# V1_0.net
KiCad netlist of a schematic drawn in Altium Designer
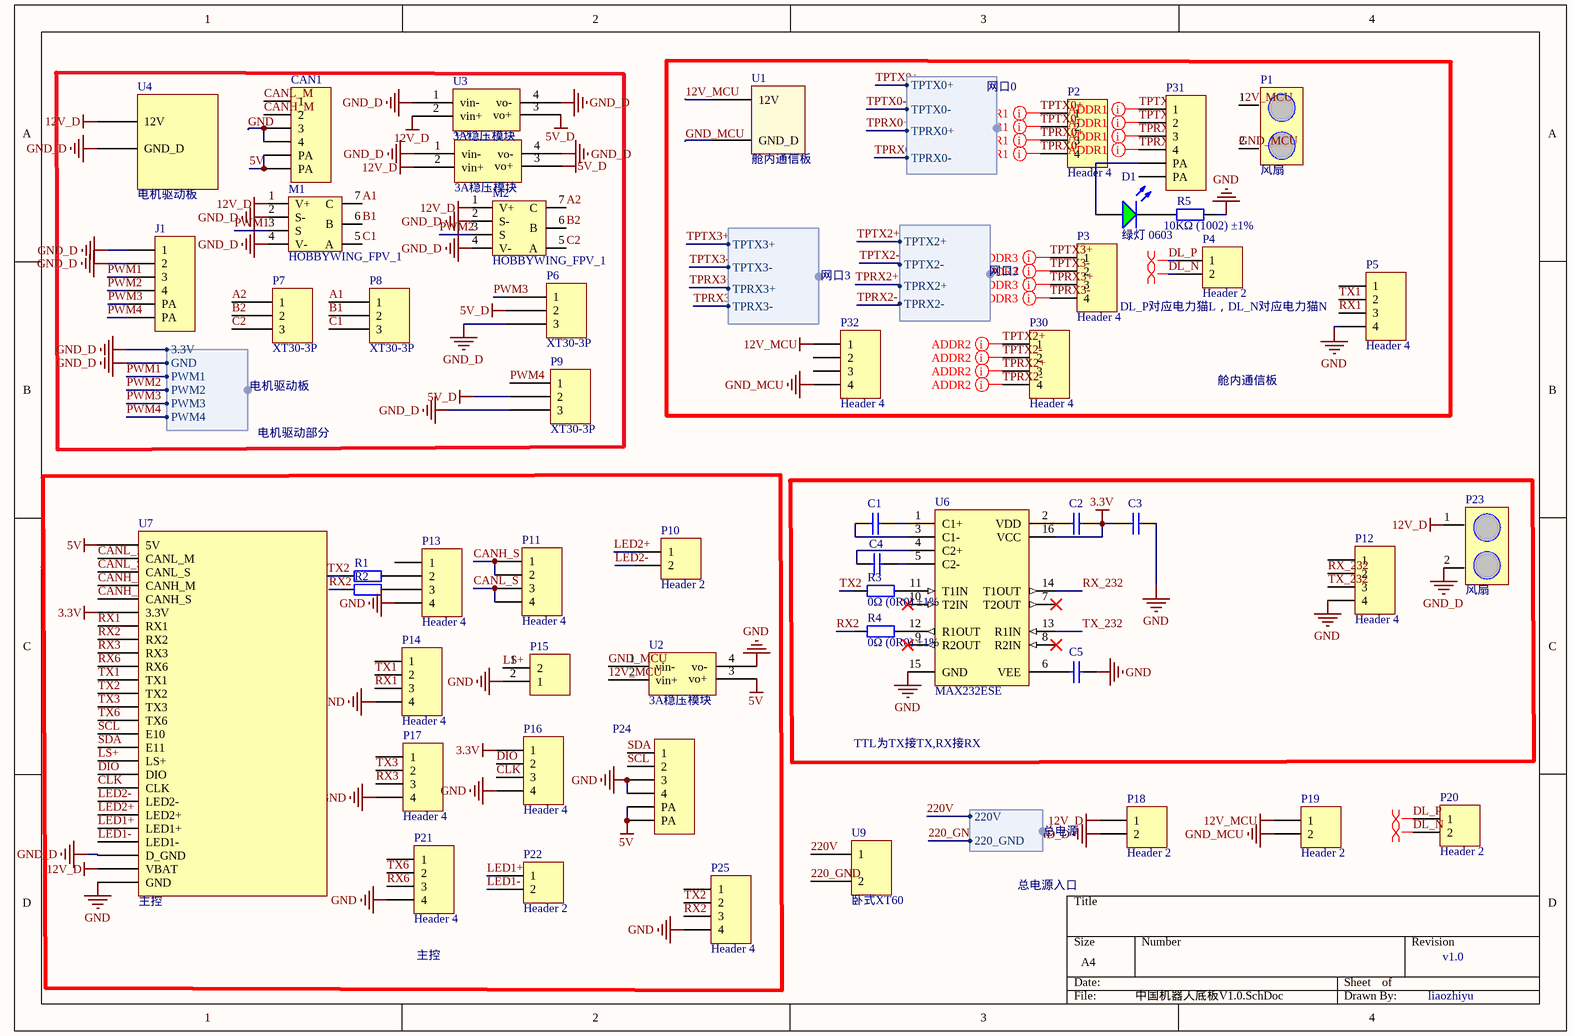
[diagram p0: 中国机器人底板V1.0.SchDoc]

(export (version "E")
  (design (tool "Eeschema 10.0.6"))
  (components
    (comp (ref "C1")
      (value "100nF (104) 10% 50V")
      (footprint "0603_C")
      (description "贴片电容")
      (libsource (lib "Miscellaneous Devices LC") (part "0603 100nF (104) 10% 50V"))
    )
    (comp (ref "C2")
      (value "100nF (104) 10% 50V")
      (footprint "0603_C")
      (description "贴片电容")
      (libsource (lib "Miscellaneous Devices LC") (part "0603 100nF (104) 10% 50V"))
    )
    (comp (ref "C3")
      (value "100nF (104) 10% 50V")
      (footprint "0603_C")
      (description "贴片电容")
      (libsource (lib "Miscellaneous Devices LC") (part "0603 100nF (104) 10% 50V"))
    )
    (comp (ref "C4")
      (value "100nF (104) 10% 50V")
      (footprint "0603_C")
      (description "贴片电容")
      (libsource (lib "Miscellaneous Devices LC") (part "0603 100nF (104) 10% 50V"))
    )
    (comp (ref "C5")
      (value "100nF (104) 10% 50V")
      (footprint "0603_C")
      (description "贴片电容")
      (libsource (lib "Miscellaneous Devices LC") (part "0603 100nF (104) 10% 50V"))
    )
    (comp (ref "CAN1")
      (value "Header 6")
      (footprint "Modolex_6P")
      (description "Header, 6-Pin")
      (fields (field (name "PUBLISHER") "Altium Limited"))
      (libsource (lib "无刷电机驱动") (part "Header 6"))
    )
    (comp (ref "D1")
      (value "绿灯 0603")
      (footprint "0603_LED_S1")
      (description "发光二极管")
      (libsource (lib "F4主控") (part "0603 绿灯"))
    )
    (comp (ref "J1")
      (value "Header 6")
      (footprint "Modolex_6P")
      (description "Header, 6-Pin")
      (fields (field (name "PUBLISHER") "Altium Limited"))
      (libsource (lib "AUV_BOTTOM") (part "Header 6"))
    )
    (comp (ref "M1")
      (value "HOBBYWING_FPV_1")
      (footprint "HOBBYWING_WING20A/30A")
      (libsource (lib "无刷电机驱动") (part "HOBBYWING_FPV_1"))
    )
    (comp (ref "M2")
      (value "HOBBYWING_FPV_1")
      (footprint "HOBBYWING_WING20A/30A")
      (libsource (lib "无刷电机驱动") (part "HOBBYWING_FPV_1"))
    )
    (comp (ref "P1") (value "风扇") (footprint "风扇接口") (libsource (lib "ROV2019V2.0") (part "风扇")))
    (comp (ref "P2")
      (value "Header 4")
      (footprint "Molex-4")
      (description "Header, 4-Pin")
      (fields (field (name "PUBLISHER") "Altium Limited"))
      (libsource (lib "AUV_BOTTOM") (part "Header 4"))
    )
    (comp (ref "P3")
      (value "Header 4")
      (footprint "Molex-4")
      (description "Header, 4-Pin")
      (fields (field (name "PUBLISHER") "Altium Limited"))
      (libsource (lib "AUV_BOTTOM") (part "Header 4"))
    )
    (comp (ref "P4")
      (value "Header 2")
      (footprint "XT30 - 2")
      (description "Header, 2-Pin")
      (fields (field (name "PUBLISHER") "Altium Limited"))
      (libsource (lib "无刷电机驱动") (part "Header 2"))
    )
    (comp (ref "P5")
      (value "Header 4")
      (footprint "Molex-4")
      (description "Header, 4-Pin")
      (fields (field (name "PUBLISHER") "Altium Limited"))
      (libsource (lib "AUV_BOTTOM") (part "Header 4"))
    )
    (comp (ref "P6")
      (value "XT30-3P")
      (footprint "XT30-3P")
      (libsource (lib "Integrated_Library") (part "XT30-3P"))
    )
    (comp (ref "P7")
      (value "XT30-3P")
      (footprint "XT30-3P")
      (libsource (lib "Integrated_Library") (part "XT30-3P"))
    )
    (comp (ref "P8")
      (value "XT30-3P")
      (footprint "XT30-3P")
      (libsource (lib "Integrated_Library") (part "XT30-3P"))
    )
    (comp (ref "P9")
      (value "XT30-3P")
      (footprint "XT30-3P")
      (libsource (lib "Integrated_Library") (part "XT30-3P"))
    )
    (comp (ref "P10")
      (value "Header 2")
      (footprint "XT30 - 2")
      (description "Header, 2-Pin")
      (fields (field (name "PUBLISHER") "Altium Limited"))
      (libsource (lib "无刷电机驱动") (part "Header 2"))
    )
    (comp (ref "P11")
      (value "Header 4")
      (footprint "Molex-4")
      (description "Header, 4-Pin")
      (fields (field (name "PUBLISHER") "Altium Limited"))
      (libsource (lib "AUV_BOTTOM") (part "Header 4"))
    )
    (comp (ref "P12")
      (value "Header 4")
      (footprint "Molex-4")
      (description "Header, 4-Pin")
      (fields (field (name "PUBLISHER") "Altium Limited"))
      (libsource (lib "AUV_BOTTOM") (part "Header 4"))
    )
    (comp (ref "P13")
      (value "Header 4")
      (footprint "Molex-4")
      (description "Header, 4-Pin")
      (fields (field (name "PUBLISHER") "Altium Limited"))
      (libsource (lib "AUV_BOTTOM") (part "Header 4"))
    )
    (comp (ref "P14")
      (value "Header 4")
      (footprint "Molex-4")
      (description "Header, 4-Pin")
      (fields (field (name "PUBLISHER") "Altium Limited"))
      (libsource (lib "AUV_BOTTOM") (part "Header 4"))
    )
    (comp (ref "P15")
      (value "Header 2")
      (footprint "XT30 - 2")
      (description "Header, 2-Pin")
      (fields (field (name "PUBLISHER") "Altium Limited"))
      (libsource (lib "AUV_BOTTOM") (part "Header 2"))
    )
    (comp (ref "P16")
      (value "Header 4")
      (footprint "Molex-4")
      (description "Header, 4-Pin")
      (fields (field (name "PUBLISHER") "Altium Limited"))
      (libsource (lib "AUV_BOTTOM") (part "Header 4"))
    )
    (comp (ref "P17")
      (value "Header 4")
      (footprint "Molex-4")
      (description "Header, 4-Pin")
      (fields (field (name "PUBLISHER") "Altium Limited"))
      (libsource (lib "AUV_BOTTOM") (part "Header 4"))
    )
    (comp (ref "P18")
      (value "Header 2")
      (footprint "XT30 - 2")
      (description "Header, 2-Pin")
      (fields (field (name "PUBLISHER") "Altium Limited"))
      (libsource (lib "无刷电机驱动") (part "Header 2"))
    )
    (comp (ref "P19")
      (value "Header 2")
      (footprint "XT30 - 2")
      (description "Header, 2-Pin")
      (fields (field (name "PUBLISHER") "Altium Limited"))
      (libsource (lib "无刷电机驱动") (part "Header 2"))
    )
    (comp (ref "P20")
      (value "Header 2")
      (footprint "XT30 - 2")
      (description "Header, 2-Pin")
      (fields (field (name "PUBLISHER") "Altium Limited"))
      (libsource (lib "无刷电机驱动") (part "Header 2"))
    )
    (comp (ref "P21")
      (value "Header 4")
      (footprint "Molex-4")
      (description "Header, 4-Pin")
      (fields (field (name "PUBLISHER") "Altium Limited"))
      (libsource (lib "AUV_BOTTOM") (part "Header 4"))
    )
    (comp (ref "P22")
      (value "Header 2")
      (footprint "XT30 - 2")
      (description "Header, 2-Pin")
      (fields (field (name "PUBLISHER") "Altium Limited"))
      (libsource (lib "无刷电机驱动") (part "Header 2"))
    )
    (comp (ref "P23") (value "风扇") (footprint "风扇接口") (libsource (lib "ROV2019V2.0") (part "风扇")))
    (comp (ref "P24")
      (value "Header 6")
      (footprint "Modolex_6P")
      (description "Header, 6-Pin")
      (fields (field (name "PUBLISHER") "Altium Limited"))
      (libsource (lib "无刷电机驱动") (part "Header 6"))
    )
    (comp (ref "P25")
      (value "Header 4")
      (footprint "Molex-4")
      (description "Header, 4-Pin")
      (fields (field (name "PUBLISHER") "Altium Limited"))
      (libsource (lib "AUV_BOTTOM") (part "Header 4"))
    )
    (comp (ref "P30")
      (value "Header 4")
      (footprint "Molex-4")
      (description "Header, 4-Pin")
      (fields (field (name "PUBLISHER") "Altium Limited"))
      (libsource (lib "AUV_BOTTOM") (part "Header 4"))
    )
    (comp (ref "P31")
      (value "Header 6")
      (footprint "Modolex_6P")
      (description "Header, 6-Pin")
      (fields (field (name "PUBLISHER") "Altium Limited"))
      (libsource (lib "AUV_BOTTOM") (part "Header 6"))
    )
    (comp (ref "P32")
      (value "Header 4")
      (footprint "Molex-4")
      (description "Header, 4-Pin")
      (fields (field (name "PUBLISHER") "Altium Limited"))
      (libsource (lib "AUV_BOTTOM") (part "Header 4"))
    )
    (comp (ref "R1")
      (value "0Ω (0R0) ±1%")
      (footprint "0603_R")
      (description "贴片电阻")
      (libsource (lib "Miscellaneous Devices LC") (part "0603 0Ω (0R0) 1%"))
    )
    (comp (ref "R2")
      (value "0Ω (0R0) ±1%")
      (footprint "0603_R")
      (description "贴片电阻")
      (libsource (lib "Miscellaneous Devices LC") (part "0603 0Ω (0R0) 1%"))
    )
    (comp (ref "R3")
      (value "0Ω (0R0) ±1%")
      (footprint "0603_R")
      (description "贴片电阻")
      (libsource (lib "Miscellaneous Devices LC") (part "0603 0Ω (0R0) 1%"))
    )
    (comp (ref "R4")
      (value "0Ω (0R0) ±1%")
      (footprint "0603_R")
      (description "贴片电阻")
      (libsource (lib "Miscellaneous Devices LC") (part "0603 0Ω (0R0) 1%"))
    )
    (comp (ref "R5")
      (value "10KΩ (1002) ±1%")
      (footprint "0603_R")
      (description "贴片电阻")
      (libsource (lib "转接板") (part "0603 10KΩ (1002) 1%"))
    )
    (comp (ref "U1")
      (value "舱内通信板")
      (footprint "舱内通信板")
      (libsource (lib "Integrated_Library") (part "舱内通信板"))
    )
    (comp (ref "U2") (value "3A稳压模块") (footprint "稳压模块") (libsource (lib "转接板") (part "可调稳压芯片")))
    (comp (ref "U3") (value "3A稳压模块") (footprint "稳压模块") (libsource (lib "转接板") (part "可调稳压芯片")))
    (comp (ref "U4")
      (value "电机驱动板")
      (footprint "电机驱动板")
      (libsource (lib "Integrated_Library") (part "电机驱动板"))
    )
    (comp (ref "U5") (value "3A稳压模块") (footprint "稳压模块") (libsource (lib "转接板") (part "可调稳压芯片")))
    (comp (ref "U6")
      (value "MAX232ESE")
      (footprint "SOIC-16_150mil")
      (description "RS232")
      (libsource (lib "Miscellaneous Devices LC") (part "MAX232ESE_[C26860]"))
    )
    (comp (ref "U7") (value "主控") (footprint "主控") (libsource (lib "Integrated_Library") (part "主控")))
    (comp (ref "U9")
      (value "卧式XT60")
      (footprint "卧式XT60")
      (libsource (lib "Integrated_Library") (part "卧式XT60"))
    )
  )
  (nets
    (net (code "1") (name "/220V") (class "Default")
      (node (ref "U9") (pin "1") (pinfunction "1_1") (pintype "passive"))
    )
    (net (code "2") (name "/220_GND") (class "Default")
      (node (ref "U9") (pin "2") (pinfunction "2_2") (pintype "passive"))
    )
    (net (code "3") (name "/A1") (class "Default")
      (node (ref "M1") (pin "7") (pinfunction "C_7") (pintype "passive"))
      (node (ref "P8") (pin "1") (pinfunction "1_1") (pintype "passive"))
    )
    (net (code "4") (name "/A2") (class "Default")
      (node (ref "M2") (pin "7") (pinfunction "C_7") (pintype "passive"))
      (node (ref "P7") (pin "1") (pinfunction "1_1") (pintype "passive"))
    )
    (net (code "5") (name "/B1") (class "Default")
      (node (ref "M1") (pin "6") (pinfunction "B_6") (pintype "passive"))
      (node (ref "P8") (pin "2") (pinfunction "2_2") (pintype "passive"))
    )
    (net (code "6") (name "/B2") (class "Default")
      (node (ref "M2") (pin "6") (pinfunction "B_6") (pintype "passive"))
      (node (ref "P7") (pin "2") (pinfunction "2_2") (pintype "passive"))
    )
    (net (code "7") (name "/C1") (class "Default")
      (node (ref "M1") (pin "5") (pinfunction "A_5") (pintype "passive"))
      (node (ref "P8") (pin "3") (pinfunction "3_3") (pintype "passive"))
    )
    (net (code "8") (name "/C2") (class "Default")
      (node (ref "M2") (pin "5") (pinfunction "A_5") (pintype "passive"))
      (node (ref "P7") (pin "3") (pinfunction "3_3") (pintype "passive"))
    )
    (net (code "9") (name "/CANH_M") (class "Default")
      (node (ref "CAN1") (pin "2") (pinfunction "2_2") (pintype "passive"))
      (node (ref "U7") (pin "4") (pinfunction "CANH_M_4") (pintype "passive"))
    )
    (net (code "10") (name "/CANH_S") (class "Default")
      (node (ref "P11") (pin "1") (pinfunction "1_1") (pintype "passive"))
      (node (ref "P11") (pin "2") (pinfunction "2_2") (pintype "passive"))
      (node (ref "U7") (pin "5") (pinfunction "CANH_S_5") (pintype "passive"))
    )
    (net (code "11") (name "/CANL_M") (class "Default")
      (node (ref "CAN1") (pin "1") (pinfunction "1_1") (pintype "passive"))
      (node (ref "U7") (pin "2") (pinfunction "CANL_M_2") (pintype "passive"))
    )
    (net (code "12") (name "/CANL_S") (class "Default")
      (node (ref "P11") (pin "3") (pinfunction "3_3") (pintype "passive"))
      (node (ref "P11") (pin "4") (pinfunction "4_4") (pintype "passive"))
      (node (ref "U7") (pin "3") (pinfunction "CANL_S_3") (pintype "passive"))
    )
    (net (code "13") (name "/CLK") (class "Default")
      (node (ref "P16") (pin "3") (pinfunction "3_3") (pintype "passive"))
      (node (ref "U7") (pin "19") (pinfunction "CLK_19") (pintype "passive"))
    )
    (net (code "14") (name "/DIO") (class "Default")
      (node (ref "P16") (pin "2") (pinfunction "2_2") (pintype "passive"))
      (node (ref "U7") (pin "18") (pinfunction "DIO_18") (pintype "passive"))
    )
    (net (code "15") (name "/DL_N") (class "Default")
      (node (ref "P20") (pin "2") (pinfunction "2_2") (pintype "passive"))
      (node (ref "P4") (pin "2") (pinfunction "2_2") (pintype "passive"))
    )
    (net (code "16") (name "/DL_P") (class "Default")
      (node (ref "P20") (pin "1") (pinfunction "1_1") (pintype "passive"))
      (node (ref "P4") (pin "1") (pinfunction "1_1") (pintype "passive"))
    )
    (net (code "17") (name "/LED1+") (class "Default")
      (node (ref "P22") (pin "1") (pinfunction "1_1") (pintype "passive"))
      (node (ref "U7") (pin "22") (pinfunction "LED1+_22") (pintype "passive"))
    )
    (net (code "18") (name "/LED1-") (class "Default")
      (node (ref "P22") (pin "2") (pinfunction "2_2") (pintype "passive"))
      (node (ref "U7") (pin "23") (pinfunction "LED1-_23") (pintype "passive"))
    )
    (net (code "19") (name "/LED2+") (class "Default")
      (node (ref "P10") (pin "1") (pinfunction "1_1") (pintype "passive"))
      (node (ref "U7") (pin "21") (pinfunction "LED2+_21") (pintype "passive"))
    )
    (net (code "20") (name "/LED2-") (class "Default")
      (node (ref "P10") (pin "2") (pinfunction "2_2") (pintype "passive"))
      (node (ref "U7") (pin "20") (pinfunction "LED2-_20") (pintype "passive"))
    )
    (net (code "21") (name "/LS+") (class "Default")
      (node (ref "P15") (pin "1") (pinfunction "2_1") (pintype "passive"))
      (node (ref "U7") (pin "17") (pinfunction "LS+_17") (pintype "passive"))
    )
    (net (code "22") (name "/PWM1") (class "Default")
      (node (ref "J1") (pin "3") (pinfunction "3_3") (pintype "passive"))
      (node (ref "M1") (pin "3") (pinfunction "S_3") (pintype "passive"))
    )
    (net (code "23") (name "/PWM2") (class "Default")
      (node (ref "J1") (pin "4") (pinfunction "4_4") (pintype "passive"))
      (node (ref "M2") (pin "3") (pinfunction "S_3") (pintype "passive"))
    )
    (net (code "24") (name "/PWM3") (class "Default")
      (node (ref "J1") (pin "5") (pinfunction "PA_5") (pintype "passive"))
      (node (ref "P6") (pin "1") (pinfunction "1_1") (pintype "passive"))
    )
    (net (code "25") (name "/PWM4") (class "Default")
      (node (ref "J1") (pin "6") (pinfunction "PA_6") (pintype "passive"))
      (node (ref "P9") (pin "1") (pinfunction "1_1") (pintype "passive"))
    )
    (net (code "26") (name "/RX1") (class "Default")
      (node (ref "P14") (pin "3") (pinfunction "3_3") (pintype "passive"))
      (node (ref "P5") (pin "3") (pinfunction "3_3") (pintype "passive"))
      (node (ref "U7") (pin "7") (pinfunction "RX1_7") (pintype "passive"))
    )
    (net (code "27") (name "/RX2") (class "Default")
      (node (ref "P25") (pin "3") (pinfunction "3_3") (pintype "passive"))
      (node (ref "R2") (pin "1") (pinfunction "1_1") (pintype "passive"))
      (node (ref "R4") (pin "1") (pinfunction "1_1") (pintype "passive"))
      (node (ref "U7") (pin "8") (pinfunction "RX2_8") (pintype "passive"))
    )
    (net (code "28") (name "/RX3") (class "Default")
      (node (ref "P17") (pin "3") (pinfunction "3_3") (pintype "passive"))
      (node (ref "U7") (pin "9") (pinfunction "RX3_9") (pintype "passive"))
    )
    (net (code "29") (name "/RX6") (class "Default")
      (node (ref "P21") (pin "3") (pinfunction "3_3") (pintype "passive"))
      (node (ref "U7") (pin "10") (pinfunction "RX6_10") (pintype "passive"))
    )
    (net (code "30") (name "/RX_232") (class "Default")
      (node (ref "P12") (pin "2") (pinfunction "2_2") (pintype "passive"))
      (node (ref "U6") (pin "14") (pinfunction "T1OUT_14") (pintype "output"))
    )
    (net (code "31") (name "/SCL") (class "Default")
      (node (ref "P24") (pin "2") (pinfunction "2_2") (pintype "passive"))
      (node (ref "U7") (pin "15") (pinfunction "E10_15") (pintype "passive"))
    )
    (net (code "32") (name "/SDA") (class "Default")
      (node (ref "P24") (pin "1") (pinfunction "1_1") (pintype "passive"))
      (node (ref "U7") (pin "16") (pinfunction "E11_16") (pintype "passive"))
    )
    (net (code "33") (name "/TPRX0+") (class "Default")
      (node (ref "P2") (pin "3") (pinfunction "3_3") (pintype "passive"))
      (node (ref "P31") (pin "3") (pinfunction "3_3") (pintype "passive"))
    )
    (net (code "34") (name "/TPRX0-") (class "Default")
      (node (ref "P2") (pin "4") (pinfunction "4_4") (pintype "passive"))
      (node (ref "P31") (pin "4") (pinfunction "4_4") (pintype "passive"))
    )
    (net (code "35") (name "/TPRX2+") (class "Default")
      (node (ref "P30") (pin "3") (pinfunction "3_3") (pintype "passive"))
    )
    (net (code "36") (name "/TPRX2-") (class "Default")
      (node (ref "P30") (pin "4") (pinfunction "4_4") (pintype "passive"))
    )
    (net (code "37") (name "/TPRX3+") (class "Default")
      (node (ref "P3") (pin "3") (pinfunction "3_3") (pintype "passive"))
    )
    (net (code "38") (name "/TPRX3-") (class "Default")
      (node (ref "P3") (pin "4") (pinfunction "4_4") (pintype "passive"))
    )
    (net (code "39") (name "/TPTX0+") (class "Default")
      (node (ref "P2") (pin "1") (pinfunction "1_1") (pintype "passive"))
      (node (ref "P31") (pin "1") (pinfunction "1_1") (pintype "passive"))
    )
    (net (code "40") (name "/TPTX0-") (class "Default")
      (node (ref "P2") (pin "2") (pinfunction "2_2") (pintype "passive"))
      (node (ref "P31") (pin "2") (pinfunction "2_2") (pintype "passive"))
    )
    (net (code "41") (name "/TPTX2+") (class "Default")
      (node (ref "P30") (pin "1") (pinfunction "1_1") (pintype "passive"))
    )
    (net (code "42") (name "/TPTX2-") (class "Default")
      (node (ref "P30") (pin "2") (pinfunction "2_2") (pintype "passive"))
    )
    (net (code "43") (name "/TPTX3+") (class "Default")
      (node (ref "P3") (pin "1") (pinfunction "1_1") (pintype "passive"))
    )
    (net (code "44") (name "/TPTX3-") (class "Default")
      (node (ref "P3") (pin "2") (pinfunction "2_2") (pintype "passive"))
    )
    (net (code "45") (name "/TX1") (class "Default")
      (node (ref "P14") (pin "2") (pinfunction "2_2") (pintype "passive"))
      (node (ref "P5") (pin "2") (pinfunction "2_2") (pintype "passive"))
      (node (ref "U7") (pin "11") (pinfunction "TX1_11") (pintype "passive"))
    )
    (net (code "46") (name "/TX2") (class "Default")
      (node (ref "P25") (pin "2") (pinfunction "2_2") (pintype "passive"))
      (node (ref "R1") (pin "1") (pinfunction "1_1") (pintype "passive"))
      (node (ref "R3") (pin "1") (pinfunction "1_1") (pintype "passive"))
      (node (ref "U7") (pin "12") (pinfunction "TX2_12") (pintype "passive"))
    )
    (net (code "47") (name "/TX3") (class "Default")
      (node (ref "P17") (pin "2") (pinfunction "2_2") (pintype "passive"))
      (node (ref "U7") (pin "13") (pinfunction "TX3_13") (pintype "passive"))
    )
    (net (code "48") (name "/TX6") (class "Default")
      (node (ref "P21") (pin "2") (pinfunction "2_2") (pintype "passive"))
      (node (ref "U7") (pin "14") (pinfunction "TX6_14") (pintype "passive"))
    )
    (net (code "49") (name "/TX_232") (class "Default")
      (node (ref "P12") (pin "3") (pinfunction "3_3") (pintype "passive"))
      (node (ref "U6") (pin "13") (pinfunction "R1IN_13") (pintype "input"))
    )
    (net (code "50") (name "3.3V") (class "Default")
      (node (ref "C2") (pin "2") (pinfunction "2_2") (pintype "passive"))
      (node (ref "C3") (pin "1") (pinfunction "1_1") (pintype "passive"))
      (node (ref "P16") (pin "1") (pinfunction "1_1") (pintype "passive"))
      (node (ref "U6") (pin "16") (pinfunction "VCC_16") (pintype "power_in"))
      (node (ref "U7") (pin "6") (pinfunction "3.3V_6") (pintype "passive"))
    )
    (net (code "51") (name "5V") (class "Default")
      (node (ref "CAN1") (pin "5") (pinfunction "PA_5") (pintype "passive"))
      (node (ref "CAN1") (pin "6") (pinfunction "PA_6") (pintype "passive"))
      (node (ref "P24") (pin "5") (pinfunction "PA_5") (pintype "passive"))
      (node (ref "P24") (pin "6") (pinfunction "PA_6") (pintype "passive"))
      (node (ref "U2") (pin "3") (pinfunction "vo+_3") (pintype "passive"))
      (node (ref "U7") (pin "1") (pinfunction "5V_1") (pintype "passive"))
    )
    (net (code "52") (name "5V_D") (class "Default")
      (node (ref "P6") (pin "2") (pinfunction "2_2") (pintype "passive"))
      (node (ref "P9") (pin "2") (pinfunction "2_2") (pintype "passive"))
      (node (ref "U3") (pin "3") (pinfunction "vo+_3") (pintype "passive"))
      (node (ref "U5") (pin "3") (pinfunction "vo+_3") (pintype "passive"))
    )
    (net (code "53") (name "12V_D") (class "Default")
      (node (ref "M1") (pin "1") (pinfunction "V+_1") (pintype "passive"))
      (node (ref "M2") (pin "1") (pinfunction "V+_1") (pintype "passive"))
      (node (ref "P18") (pin "1") (pinfunction "1_1") (pintype "passive"))
      (node (ref "P23") (pin "1") (pintype "passive"))
      (node (ref "U3") (pin "2") (pinfunction "vin+_2") (pintype "passive"))
      (node (ref "U4") (pin "1") (pinfunction "12V_1") (pintype "passive"))
      (node (ref "U5") (pin "2") (pinfunction "vin+_2") (pintype "passive"))
      (node (ref "U7") (pin "25") (pinfunction "VBAT_25") (pintype "passive"))
    )
    (net (code "54") (name "12V_MCU") (class "Default")
      (node (ref "P1") (pin "1") (pintype "passive"))
      (node (ref "P19") (pin "1") (pinfunction "1_1") (pintype "passive"))
      (node (ref "P32") (pin "1") (pinfunction "1_1") (pintype "passive"))
      (node (ref "U1") (pin "1") (pinfunction "12V_1") (pintype "passive"))
      (node (ref "U2") (pin "2") (pinfunction "vin+_2") (pintype "passive"))
    )
    (net (code "55") (name "GND") (class "Default")
      (node (ref "C3") (pin "2") (pinfunction "2_2") (pintype "passive"))
      (node (ref "C5") (pin "2") (pinfunction "2_2") (pintype "passive"))
      (node (ref "CAN1") (pin "3") (pinfunction "3_3") (pintype "passive"))
      (node (ref "CAN1") (pin "4") (pinfunction "4_4") (pintype "passive"))
      (node (ref "P12") (pin "4") (pinfunction "4_4") (pintype "passive"))
      (node (ref "P13") (pin "4") (pinfunction "4_4") (pintype "passive"))
      (node (ref "P14") (pin "4") (pinfunction "4_4") (pintype "passive"))
      (node (ref "P15") (pin "2") (pinfunction "1_2") (pintype "passive"))
      (node (ref "P16") (pin "4") (pinfunction "4_4") (pintype "passive"))
      (node (ref "P17") (pin "4") (pinfunction "4_4") (pintype "passive"))
      (node (ref "P21") (pin "4") (pinfunction "4_4") (pintype "passive"))
      (node (ref "P24") (pin "3") (pinfunction "3_3") (pintype "passive"))
      (node (ref "P24") (pin "4") (pinfunction "4_4") (pintype "passive"))
      (node (ref "P25") (pin "4") (pinfunction "4_4") (pintype "passive"))
      (node (ref "P5") (pin "4") (pinfunction "4_4") (pintype "passive"))
      (node (ref "R5") (pin "2") (pinfunction "2_2") (pintype "passive"))
      (node (ref "U2") (pin "4") (pinfunction "vo-_4") (pintype "passive"))
      (node (ref "U6") (pin "15") (pinfunction "GND_15") (pintype "power_in"))
      (node (ref "U7") (pin "26") (pinfunction "GND_26") (pintype "passive"))
    )
    (net (code "56") (name "GND_D") (class "Default")
      (node (ref "J1") (pin "1") (pinfunction "1_1") (pintype "passive"))
      (node (ref "J1") (pin "2") (pinfunction "2_2") (pintype "passive"))
      (node (ref "M1") (pin "2") (pinfunction "S-_2") (pintype "passive"))
      (node (ref "M1") (pin "4") (pinfunction "V-_4") (pintype "passive"))
      (node (ref "M2") (pin "2") (pinfunction "S-_2") (pintype "passive"))
      (node (ref "M2") (pin "4") (pinfunction "V-_4") (pintype "passive"))
      (node (ref "P18") (pin "2") (pinfunction "2_2") (pintype "passive"))
      (node (ref "P23") (pin "2") (pintype "passive"))
      (node (ref "P6") (pin "3") (pinfunction "3_3") (pintype "passive"))
      (node (ref "P9") (pin "3") (pinfunction "3_3") (pintype "passive"))
      (node (ref "U3") (pin "1") (pinfunction "vin-_1") (pintype "passive"))
      (node (ref "U3") (pin "4") (pinfunction "vo-_4") (pintype "passive"))
      (node (ref "U4") (pin "2") (pinfunction "GND_D_2") (pintype "passive"))
      (node (ref "U5") (pin "1") (pinfunction "vin-_1") (pintype "passive"))
      (node (ref "U5") (pin "4") (pinfunction "vo-_4") (pintype "passive"))
      (node (ref "U7") (pin "24") (pinfunction "D_GND_24") (pintype "passive"))
    )
    (net (code "57") (name "GND_MCU") (class "Default")
      (node (ref "P1") (pin "2") (pintype "passive"))
      (node (ref "P19") (pin "2") (pinfunction "2_2") (pintype "passive"))
      (node (ref "P32") (pin "4") (pinfunction "4_4") (pintype "passive"))
      (node (ref "U1") (pin "2") (pinfunction "GND_D_2") (pintype "passive"))
      (node (ref "U2") (pin "1") (pinfunction "vin-_1") (pintype "passive"))
    )
    (net (code "58") (name "Net-(D1-PadA)") (class "Default")
      (node (ref "D1") (pin "A") (pinfunction "A_A") (pintype "passive"))
      (node (ref "P31") (pin "5") (pinfunction "PA_5") (pintype "passive"))
    )
    (net (code "59") (name "Net-(D1-PadK)") (class "Default")
      (node (ref "D1") (pin "K") (pinfunction "K_K") (pintype "passive"))
      (node (ref "R5") (pin "1") (pinfunction "1_1") (pintype "passive"))
    )
    (net (code "60") (name "Net-(P13-Pad2)") (class "Default")
      (node (ref "P13") (pin "2") (pinfunction "2_2") (pintype "passive"))
      (node (ref "R1") (pin "2") (pinfunction "2_2") (pintype "passive"))
    )
    (net (code "61") (name "Net-(P13-Pad3)") (class "Default")
      (node (ref "P13") (pin "3") (pinfunction "3_3") (pintype "passive"))
      (node (ref "R2") (pin "2") (pinfunction "2_2") (pintype "passive"))
    )
    (net (code "62") (name "Net-(U6-C1+)") (class "Default")
      (node (ref "C1") (pin "2") (pinfunction "2_2") (pintype "passive"))
      (node (ref "U6") (pin "1") (pinfunction "C1+_1") (pintype "passive"))
    )
    (net (code "63") (name "Net-(U6-C1-)") (class "Default")
      (node (ref "C1") (pin "1") (pinfunction "1_1") (pintype "passive"))
      (node (ref "U6") (pin "3") (pinfunction "C1-_3") (pintype "passive"))
    )
    (net (code "64") (name "Net-(U6-C2+)") (class "Default")
      (node (ref "C4") (pin "1") (pinfunction "1_1") (pintype "passive"))
      (node (ref "U6") (pin "4") (pinfunction "C2+_4") (pintype "passive"))
    )
    (net (code "65") (name "Net-(U6-C2-)") (class "Default")
      (node (ref "C4") (pin "2") (pinfunction "2_2") (pintype "passive"))
      (node (ref "U6") (pin "5") (pinfunction "C2-_5") (pintype "passive"))
    )
    (net (code "66") (name "Net-(U6-R1OUT)") (class "Default")
      (node (ref "R4") (pin "2") (pinfunction "2_2") (pintype "passive"))
      (node (ref "U6") (pin "12") (pinfunction "R1OUT_12") (pintype "output"))
    )
    (net (code "67") (name "Net-(U6-T1IN)") (class "Default")
      (node (ref "R3") (pin "2") (pinfunction "2_2") (pintype "passive"))
      (node (ref "U6") (pin "11") (pinfunction "T1IN_11") (pintype "input"))
    )
    (net (code "68") (name "Net-(U6-VDD)") (class "Default")
      (node (ref "C2") (pin "1") (pinfunction "1_1") (pintype "passive"))
      (node (ref "U6") (pin "2") (pinfunction "VDD_2") (pintype "power_in"))
    )
    (net (code "69") (name "Net-(U6-VEE)") (class "Default")
      (node (ref "C5") (pin "1") (pinfunction "1_1") (pintype "passive"))
      (node (ref "U6") (pin "6") (pinfunction "VEE_6") (pintype "power_in"))
    )
    (net (code "70") (name "unconnected-(P5-Pad1)") (class "Default")
      (node (ref "P5") (pin "1") (pinfunction "1_1") (pintype "passive"))
    )
    (net (code "71") (name "unconnected-(P12-Pad1)") (class "Default")
      (node (ref "P12") (pin "1") (pinfunction "1_1") (pintype "passive"))
    )
    (net (code "72") (name "unconnected-(P13-Pad1)") (class "Default")
      (node (ref "P13") (pin "1") (pinfunction "1_1") (pintype "passive"))
    )
    (net (code "73") (name "unconnected-(P14-Pad1)") (class "Default")
      (node (ref "P14") (pin "1") (pinfunction "1_1") (pintype "passive"))
    )
    (net (code "74") (name "unconnected-(P17-Pad1)") (class "Default")
      (node (ref "P17") (pin "1") (pinfunction "1_1") (pintype "passive"))
    )
    (net (code "75") (name "unconnected-(P21-Pad1)") (class "Default")
      (node (ref "P21") (pin "1") (pinfunction "1_1") (pintype "passive"))
    )
    (net (code "76") (name "unconnected-(P25-Pad1)") (class "Default")
      (node (ref "P25") (pin "1") (pinfunction "1_1") (pintype "passive"))
    )
    (net (code "77") (name "unconnected-(P31-PA-Pad6)") (class "Default")
      (node (ref "P31") (pin "6") (pinfunction "PA_6") (pintype "passive"))
    )
    (net (code "78") (name "unconnected-(P32-Pad2)") (class "Default")
      (node (ref "P32") (pin "2") (pinfunction "2_2") (pintype "passive"))
    )
    (net (code "79") (name "unconnected-(P32-Pad3)") (class "Default")
      (node (ref "P32") (pin "3") (pinfunction "3_3") (pintype "passive"))
    )
    (net (code "80") (name "unconnected-(U6-R2IN-Pad8)") (class "Default")
      (node (ref "U6") (pin "8") (pinfunction "R2IN_8") (pintype "input+no_connect"))
    )
    (net (code "81") (name "unconnected-(U6-R2OUT-Pad9)") (class "Default")
      (node (ref "U6") (pin "9") (pinfunction "R2OUT_9") (pintype "output+no_connect"))
    )
    (net (code "82") (name "unconnected-(U6-T2IN-Pad10)") (class "Default")
      (node (ref "U6") (pin "10") (pinfunction "T2IN_10") (pintype "input+no_connect"))
    )
    (net (code "83") (name "unconnected-(U6-T2OUT-Pad7)") (class "Default")
      (node (ref "U6") (pin "7") (pinfunction "T2OUT_7") (pintype "output+no_connect"))
    )
  )
)
